# AJH_as3320_21_4hp.net
KiCad netlist of a schematic drawn in EAGLE
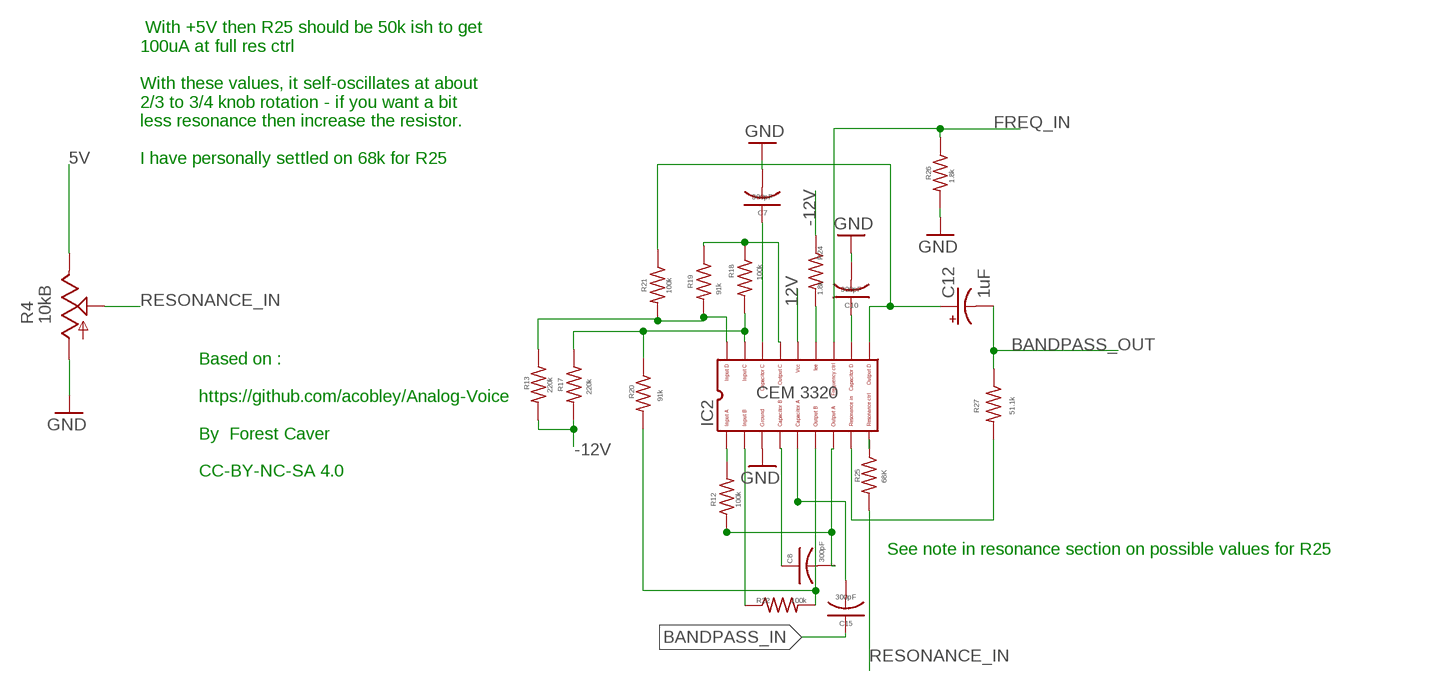
[diagram p0: schematic, sheet 1]
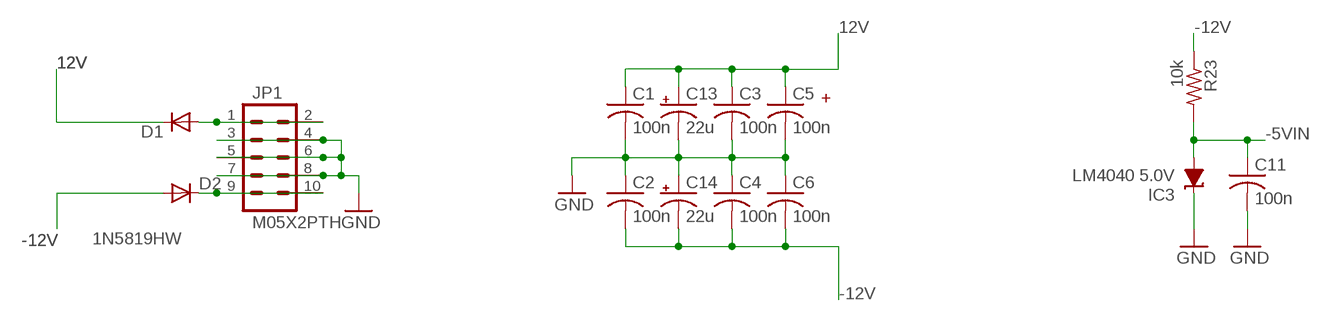
[diagram p1: schematic, sheet 2]
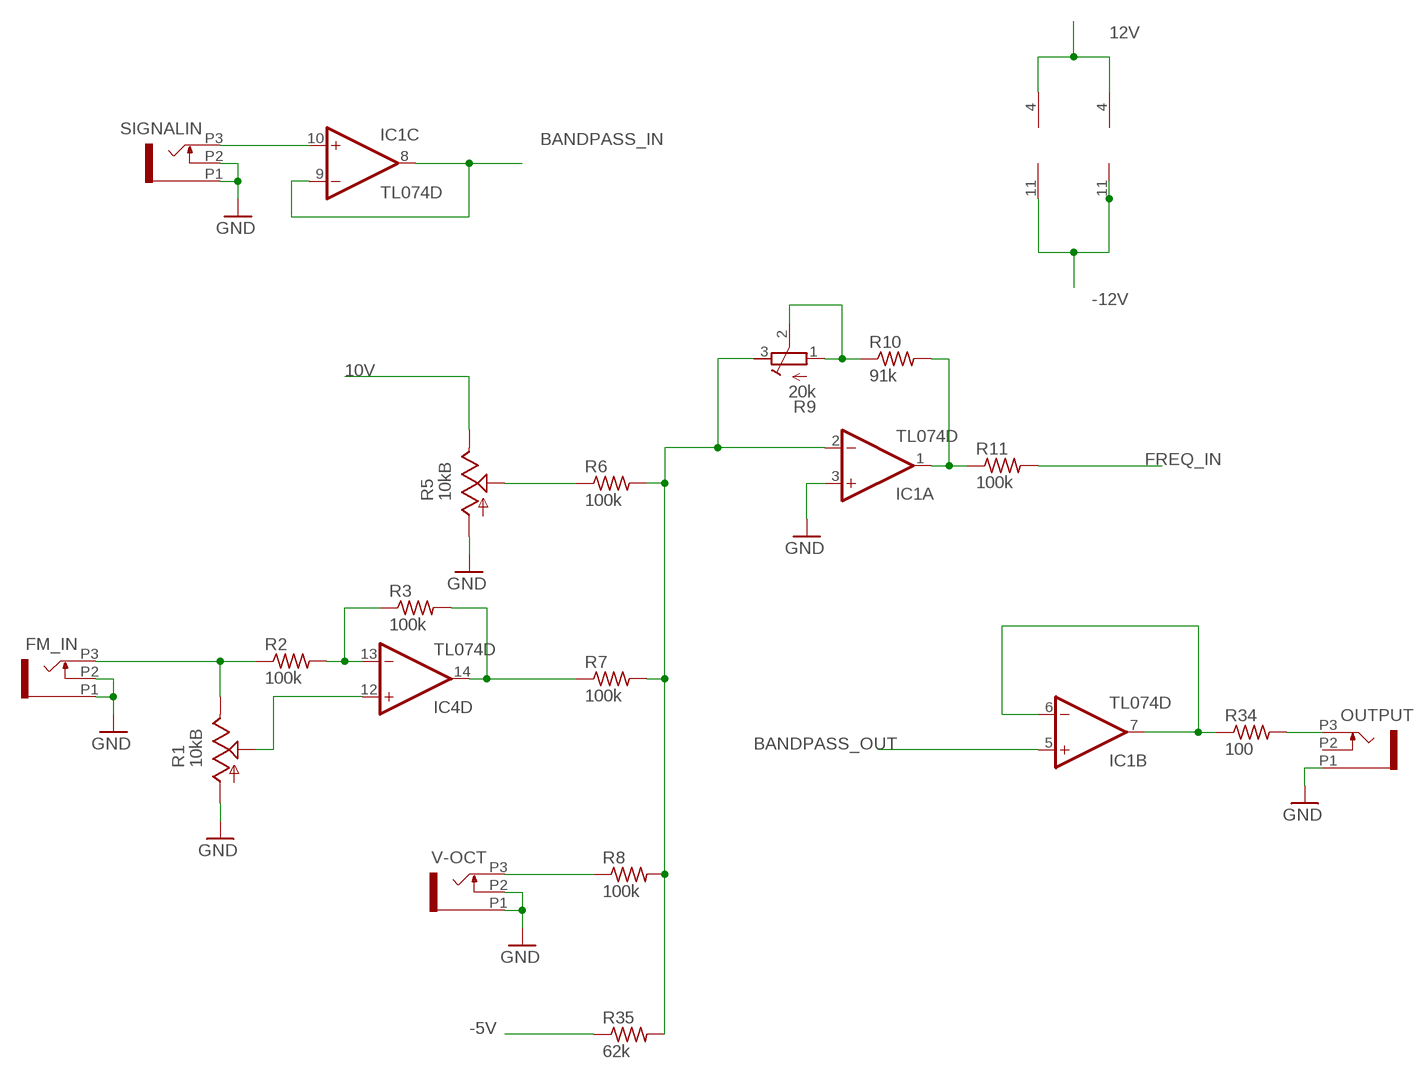
[diagram p2: schematic, sheet 3]
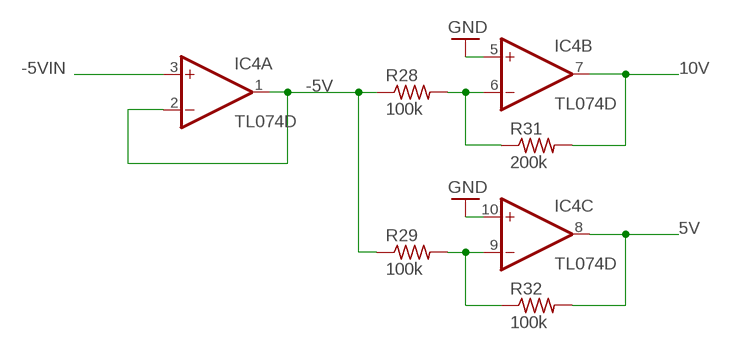
[diagram p3: schematic, sheet 4]

(export (version "E")
  (design (tool "Eeschema 10.0.6"))
  (components
    (comp (ref "IC4")
      (value "TL074D")
      (footprint "eagle-import:SO14")
      (libsource (lib "eagle-import") (part "TL074D"))
    )
    (comp (ref "R28")
      (value "100k")
      (footprint "eagle-import:R0603")
      (libsource (lib "eagle-import") (part "resistor_R-US_R0603"))
    )
    (comp (ref "R29")
      (value "100k")
      (footprint "eagle-import:R0603")
      (libsource (lib "eagle-import") (part "resistor_R-US_R0603"))
    )
    (comp (ref "R31")
      (value "200k")
      (footprint "eagle-import:R0603")
      (libsource (lib "eagle-import") (part "resistor_R-US_R0603"))
    )
    (comp (ref "R32")
      (value "100k")
      (footprint "eagle-import:R0603")
      (libsource (lib "eagle-import") (part "resistor_R-US_R0603"))
    )
    (comp (ref "FM_IN")
      (value "PJ301_THONKICONN6")
      (footprint "eagle-import:WQP_PJ_301M6")
      (libsource (lib "eagle-import") (part "PJ301_THONKICONN6"))
    )
    (comp (ref "IC1")
      (value "TL074D")
      (footprint "eagle-import:SO14")
      (libsource (lib "eagle-import") (part "TL074D"))
    )
    (comp (ref "OUTPUT")
      (value "PJ301_THONKICONN6")
      (footprint "eagle-import:WQP_PJ_301M6")
      (libsource (lib "eagle-import") (part "PJ301_THONKICONN6"))
    )
    (comp (ref "R1")
      (value "10kB")
      (footprint "eagle-import:ALPS_POT_VERTICAL")
      (libsource (lib "eagle-import") (part "POT_USVERTICAL"))
    )
    (comp (ref "R2")
      (value "100k")
      (footprint "eagle-import:R0603")
      (libsource (lib "eagle-import") (part "resistor_R-US_R0603"))
    )
    (comp (ref "R3")
      (value "100k")
      (footprint "eagle-import:R0603")
      (libsource (lib "eagle-import") (part "resistor_R-US_R0603"))
    )
    (comp (ref "R5")
      (value "10kB")
      (footprint "eagle-import:ALPS_POT_VERTICAL")
      (libsource (lib "eagle-import") (part "POT_USVERTICAL"))
    )
    (comp (ref "R6")
      (value "100k")
      (footprint "eagle-import:R0603")
      (libsource (lib "eagle-import") (part "resistor_R-US_R0603"))
    )
    (comp (ref "R7")
      (value "100k")
      (footprint "eagle-import:R0603")
      (libsource (lib "eagle-import") (part "resistor_R-US_R0603"))
    )
    (comp (ref "R8")
      (value "100k")
      (footprint "eagle-import:R0603")
      (libsource (lib "eagle-import") (part "resistor_R-US_R0603"))
    )
    (comp (ref "R9")
      (value "20k")
      (footprint "eagle-import:RTRIM3296X")
      (libsource (lib "eagle-import") (part "R-TRIMM3296X"))
    )
    (comp (ref "R10")
      (value "91k")
      (footprint "eagle-import:R0603")
      (libsource (lib "eagle-import") (part "resistor_R-US_R0603"))
    )
    (comp (ref "R11")
      (value "100k")
      (footprint "eagle-import:R0603")
      (libsource (lib "eagle-import") (part "resistor_R-US_R0603"))
    )
    (comp (ref "R34")
      (value "100")
      (footprint "eagle-import:R0603")
      (libsource (lib "eagle-import") (part "resistor_R-US_R0603"))
    )
    (comp (ref "R35")
      (value "62k")
      (footprint "eagle-import:R0603")
      (libsource (lib "eagle-import") (part "resistor_R-US_R0603"))
    )
    (comp (ref "SIGNALIN")
      (value "PJ301_THONKICONN6")
      (footprint "eagle-import:WQP_PJ_301M6")
      (libsource (lib "eagle-import") (part "PJ301_THONKICONN6"))
    )
    (comp (ref "V-OCT")
      (value "PJ301_THONKICONN6")
      (footprint "eagle-import:WQP_PJ_301M6")
      (libsource (lib "eagle-import") (part "PJ301_THONKICONN6"))
    )
    (comp (ref "C1")
      (value "100n")
      (footprint "eagle-import:C0603")
      (libsource (lib "eagle-import") (part "C-USC0603"))
    )
    (comp (ref "C2")
      (value "100n")
      (footprint "eagle-import:C0603")
      (libsource (lib "eagle-import") (part "C-USC0603"))
    )
    (comp (ref "C3")
      (value "100n")
      (footprint "eagle-import:C0603")
      (libsource (lib "eagle-import") (part "C-USC0603"))
    )
    (comp (ref "C4")
      (value "100n")
      (footprint "eagle-import:C0603")
      (libsource (lib "eagle-import") (part "C-USC0603"))
    )
    (comp (ref "C5")
      (value "100n")
      (footprint "eagle-import:C0603")
      (libsource (lib "eagle-import") (part "C-USC0603"))
    )
    (comp (ref "C6")
      (value "100n")
      (footprint "eagle-import:C0603")
      (libsource (lib "eagle-import") (part "C-USC0603"))
    )
    (comp (ref "C11")
      (value "100n")
      (footprint "eagle-import:C0603")
      (libsource (lib "eagle-import") (part "C-USC0603"))
    )
    (comp (ref "C13")
      (value "22u")
      (footprint "eagle-import:PANASONIC_B")
      (libsource (lib "eagle-import") (part "CPOL-USB"))
    )
    (comp (ref "C14")
      (value "22u")
      (footprint "eagle-import:PANASONIC_B")
      (libsource (lib "eagle-import") (part "CPOL-USB"))
    )
    (comp (ref "D1")
      (value "1N5819HW")
      (footprint "eagle-import:SOD123")
      (libsource (lib "eagle-import") (part "DIODE-SOD123"))
    )
    (comp (ref "D2")
      (value "1N5819HW")
      (footprint "eagle-import:SOD123")
      (libsource (lib "eagle-import") (part "DIODE-SOD123"))
    )
    (comp (ref "IC3")
      (value "LM4040 5.0V")
      (footprint "eagle-import:DBZ_R-PDSO-G3")
      (libsource (lib "eagle-import") (part "LM4041DBZC12"))
    )
    (comp (ref "JP1")
      (value "M05X2PTH")
      (footprint "eagle-import:AVR_ICSP")
      (libsource (lib "eagle-import") (part "M05X2PTH"))
    )
    (comp (ref "R23")
      (value "10k")
      (footprint "eagle-import:R0603")
      (libsource (lib "eagle-import") (part "resistor_R-US_R0603"))
    )
    (comp (ref "C7")
      (value "300pF")
      (footprint "eagle-import:C0603")
      (libsource (lib "eagle-import") (part "rcl_334_C-USC0603"))
    )
    (comp (ref "C8")
      (value "300pF")
      (footprint "eagle-import:C0603")
      (libsource (lib "eagle-import") (part "rcl_334_C-USC0603"))
    )
    (comp (ref "C10")
      (value "300pF")
      (footprint "eagle-import:C0603")
      (libsource (lib "eagle-import") (part "rcl_334_C-USC0603"))
    )
    (comp (ref "C12")
      (value "1uF")
      (footprint "eagle-import:PANASONIC_B")
      (libsource (lib "eagle-import") (part "rcl_334_CPOL-USB"))
    )
    (comp (ref "C15")
      (value "300pF")
      (footprint "eagle-import:C0603")
      (libsource (lib "eagle-import") (part "rcl_334_C-USC0603"))
    )
    (comp (ref "IC2")
      (value "CEM3320")
      (footprint "eagle-import:DIL18")
      (libsource (lib "eagle-import") (part "CEM3320"))
    )
    (comp (ref "R4")
      (value "10kB")
      (footprint "eagle-import:ALPS_POT_VERTICAL")
      (libsource (lib "eagle-import") (part "POT_USVERTICAL"))
    )
    (comp (ref "R12")
      (value "100k")
      (footprint "eagle-import:R0603")
      (libsource (lib "eagle-import") (part "R-US_R0603"))
    )
    (comp (ref "R13")
      (value "220k")
      (footprint "eagle-import:R0603")
      (libsource (lib "eagle-import") (part "R-US_R0603"))
    )
    (comp (ref "R17")
      (value "220k")
      (footprint "eagle-import:R0603")
      (libsource (lib "eagle-import") (part "R-US_R0603"))
    )
    (comp (ref "R18")
      (value "100k")
      (footprint "eagle-import:R0603")
      (libsource (lib "eagle-import") (part "R-US_R0603"))
    )
    (comp (ref "R19")
      (value "91k")
      (footprint "eagle-import:R0603")
      (libsource (lib "eagle-import") (part "R-US_R0603"))
    )
    (comp (ref "R20")
      (value "91k")
      (footprint "eagle-import:R0603")
      (libsource (lib "eagle-import") (part "R-US_R0603"))
    )
    (comp (ref "R21")
      (value "100k")
      (footprint "eagle-import:R0603")
      (libsource (lib "eagle-import") (part "R-US_R0603"))
    )
    (comp (ref "R22")
      (value "100k")
      (footprint "eagle-import:R0603")
      (libsource (lib "eagle-import") (part "R-US_R0603"))
    )
    (comp (ref "R24")
      (value "1.8k")
      (footprint "eagle-import:R0603")
      (libsource (lib "eagle-import") (part "R-US_R0603"))
    )
    (comp (ref "R25")
      (value "68K")
      (footprint "eagle-import:R0603")
      (libsource (lib "eagle-import") (part "R-US_R0603"))
    )
    (comp (ref "R26")
      (value "1.8k")
      (footprint "eagle-import:R0603")
      (libsource (lib "eagle-import") (part "R-US_R0603"))
    )
    (comp (ref "R27")
      (value "51.1k")
      (footprint "eagle-import:R0603")
      (libsource (lib "eagle-import") (part "R-US_R0603"))
    )
  )
  (nets
    (net (code "1") (name "-5V") (class "Default")
      (node (ref "IC4") (pin "1") (pinfunction "OUT_1") (pintype "output"))
      (node (ref "IC4") (pin "2") (pinfunction "-IN_2") (pintype "input"))
      (node (ref "R28") (pin "1") (pinfunction "1_1") (pintype "passive"))
      (node (ref "R29") (pin "1") (pinfunction "1_1") (pintype "passive"))
      (node (ref "R35") (pin "1") (pinfunction "1_1") (pintype "passive"))
    )
    (net (code "2") (name "-5VIN") (class "Default")
      (node (ref "C11") (pin "1") (pinfunction "1_1") (pintype "passive"))
      (node (ref "IC3") (pin "2") (pinfunction "A_2") (pintype "passive"))
      (node (ref "IC4") (pin "3") (pinfunction "+IN_3") (pintype "input"))
      (node (ref "R23") (pin "2") (pinfunction "2_2") (pintype "passive"))
    )
    (net (code "3") (name "-12V") (class "Default")
      (node (ref "C14") (pin "-") (pinfunction "-_-") (pintype "passive"))
      (node (ref "C2") (pin "2") (pinfunction "2_2") (pintype "passive"))
      (node (ref "C4") (pin "2") (pinfunction "2_2") (pintype "passive"))
      (node (ref "C6") (pin "2") (pinfunction "2_2") (pintype "passive"))
      (node (ref "D2") (pin "A") (pinfunction "A_A") (pintype "passive"))
      (node (ref "IC1") (pin "11") (pinfunction "V-_11") (pintype "power_in"))
      (node (ref "IC4") (pin "11") (pinfunction "V-_11") (pintype "power_in"))
      (node (ref "R13") (pin "2") (pinfunction "2_2") (pintype "passive"))
      (node (ref "R17") (pin "2") (pinfunction "2_2") (pintype "passive"))
      (node (ref "R23") (pin "1") (pinfunction "1_1") (pintype "passive"))
      (node (ref "R24") (pin "1") (pinfunction "1_1") (pintype "passive"))
    )
    (net (code "4") (name "5V") (class "Default")
      (node (ref "IC4") (pin "8") (pinfunction "OUT_8") (pintype "output"))
      (node (ref "R32") (pin "2") (pinfunction "2_2") (pintype "passive"))
      (node (ref "R4") (pin "P$1") (pinfunction "E_P$1") (pintype "passive"))
    )
    (net (code "5") (name "10V") (class "Default")
      (node (ref "IC4") (pin "7") (pinfunction "OUT_7") (pintype "output"))
      (node (ref "R31") (pin "2") (pinfunction "2_2") (pintype "passive"))
      (node (ref "R5") (pin "P$1") (pinfunction "E_P$1") (pintype "passive"))
    )
    (net (code "6") (name "12V") (class "Default")
      (node (ref "C1") (pin "1") (pinfunction "1_1") (pintype "passive"))
      (node (ref "C13") (pin "+") (pinfunction "+_+") (pintype "passive"))
      (node (ref "C3") (pin "1") (pinfunction "1_1") (pintype "passive"))
      (node (ref "C5") (pin "1") (pinfunction "1_1") (pintype "passive"))
      (node (ref "D1") (pin "C") (pinfunction "C_C") (pintype "passive"))
      (node (ref "IC1") (pin "4") (pinfunction "V+_4") (pintype "power_in"))
      (node (ref "IC2") (pin "14") (pinfunction "14_14") (pintype "power_in"))
      (node (ref "IC4") (pin "4") (pinfunction "V+_4") (pintype "power_in"))
    )
    (net (code "7") (name "BANDPASS_IN") (class "Default")
      (node (ref "C15") (pin "1") (pinfunction "1_1") (pintype "passive"))
      (node (ref "IC1") (pin "8") (pinfunction "OUT_8") (pintype "output"))
      (node (ref "IC1") (pin "9") (pinfunction "-IN_9") (pintype "input"))
    )
    (net (code "8") (name "BANDPASS_OUT") (class "Default")
      (node (ref "C12") (pin "-") (pinfunction "-_-") (pintype "passive"))
      (node (ref "IC1") (pin "5") (pinfunction "+IN_5") (pintype "input"))
      (node (ref "R27") (pin "1") (pinfunction "1_1") (pintype "passive"))
    )
    (net (code "9") (name "FREQ_IN") (class "Default")
      (node (ref "IC2") (pin "12") (pinfunction "12_12") (pintype "bidirectional"))
      (node (ref "R11") (pin "2") (pinfunction "2_2") (pintype "passive"))
      (node (ref "R26") (pin "1") (pinfunction "1_1") (pintype "passive"))
    )
    (net (code "10") (name "GND") (class "Default")
      (node (ref "C1") (pin "2") (pinfunction "2_2") (pintype "passive"))
      (node (ref "C10") (pin "2") (pinfunction "2_2") (pintype "passive"))
      (node (ref "C11") (pin "2") (pinfunction "2_2") (pintype "passive"))
      (node (ref "C13") (pin "-") (pinfunction "-_-") (pintype "passive"))
      (node (ref "C14") (pin "+") (pinfunction "+_+") (pintype "passive"))
      (node (ref "C2") (pin "1") (pinfunction "1_1") (pintype "passive"))
      (node (ref "C3") (pin "2") (pinfunction "2_2") (pintype "passive"))
      (node (ref "C4") (pin "1") (pinfunction "1_1") (pintype "passive"))
      (node (ref "C5") (pin "2") (pinfunction "2_2") (pintype "passive"))
      (node (ref "C6") (pin "1") (pinfunction "1_1") (pintype "passive"))
      (node (ref "C7") (pin "2") (pinfunction "2_2") (pintype "passive"))
      (node (ref "FM_IN") (pin "P1") (pinfunction "1_P1") (pintype "passive"))
      (node (ref "FM_IN") (pin "P2") (pinfunction "2_P2") (pintype "passive"))
      (node (ref "IC1") (pin "3") (pinfunction "+IN_3") (pintype "input"))
      (node (ref "IC2") (pin "3") (pinfunction "3_3") (pintype "power_in"))
      (node (ref "IC3") (pin "1") (pinfunction "C_1") (pintype "passive"))
      (node (ref "IC4") (pin "10") (pinfunction "+IN_10") (pintype "input"))
      (node (ref "IC4") (pin "5") (pinfunction "+IN_5") (pintype "input"))
      (node (ref "JP1") (pin "3") (pinfunction "3_3") (pintype "passive"))
      (node (ref "JP1") (pin "4") (pinfunction "4_4") (pintype "passive"))
      (node (ref "JP1") (pin "5") (pinfunction "5_5") (pintype "passive"))
      (node (ref "JP1") (pin "6") (pinfunction "6_6") (pintype "passive"))
      (node (ref "JP1") (pin "7") (pinfunction "7_7") (pintype "passive"))
      (node (ref "JP1") (pin "8") (pinfunction "8_8") (pintype "passive"))
      (node (ref "OUTPUT") (pin "P1") (pinfunction "1_P1") (pintype "passive"))
      (node (ref "R1") (pin "P$3") (pinfunction "A_P$3") (pintype "passive"))
      (node (ref "R26") (pin "2") (pinfunction "2_2") (pintype "passive"))
      (node (ref "R4") (pin "P$3") (pinfunction "A_P$3") (pintype "passive"))
      (node (ref "R5") (pin "P$3") (pinfunction "A_P$3") (pintype "passive"))
      (node (ref "SIGNALIN") (pin "P1") (pinfunction "1_P1") (pintype "passive"))
      (node (ref "SIGNALIN") (pin "P2") (pinfunction "2_P2") (pintype "passive"))
      (node (ref "V-OCT") (pin "P1") (pinfunction "1_P1") (pintype "passive"))
      (node (ref "V-OCT") (pin "P2") (pinfunction "2_P2") (pintype "passive"))
    )
    (net (code "11") (name "Net-(C7-Pad1)") (class "Default")
      (node (ref "C7") (pin "1") (pinfunction "1_1") (pintype "passive"))
      (node (ref "IC2") (pin "16") (pinfunction "16_16") (pintype "bidirectional"))
    )
    (net (code "12") (name "Net-(C8-Pad1)") (class "Default")
      (node (ref "C8") (pin "1") (pinfunction "1_1") (pintype "passive"))
      (node (ref "IC2") (pin "4") (pinfunction "4_4") (pintype "bidirectional"))
    )
    (net (code "13") (name "Net-(C8-Pad2)") (class "Default")
      (node (ref "C8") (pin "2") (pinfunction "2_2") (pintype "passive"))
      (node (ref "IC2") (pin "7") (pinfunction "7_7") (pintype "output"))
      (node (ref "R12") (pin "1") (pinfunction "1_1") (pintype "passive"))
    )
    (net (code "14") (name "Net-(C10-Pad1)") (class "Default")
      (node (ref "C10") (pin "1") (pinfunction "1_1") (pintype "passive"))
      (node (ref "IC2") (pin "11") (pinfunction "11_11") (pintype "output"))
    )
    (net (code "15") (name "Net-(C12-Pad+)") (class "Default")
      (node (ref "C12") (pin "+") (pinfunction "+_+") (pintype "passive"))
      (node (ref "IC2") (pin "10") (pinfunction "10_10") (pintype "output"))
      (node (ref "R21") (pin "1") (pinfunction "1_1") (pintype "passive"))
    )
    (net (code "16") (name "Net-(C15-Pad2)") (class "Default")
      (node (ref "C15") (pin "2") (pinfunction "2_2") (pintype "passive"))
      (node (ref "IC2") (pin "5") (pinfunction "5_5") (pintype "bidirectional"))
    )
    (net (code "17") (name "Net-(D1-PadA)") (class "Default")
      (node (ref "D1") (pin "A") (pinfunction "A_A") (pintype "passive"))
      (node (ref "JP1") (pin "1") (pinfunction "1_1") (pintype "passive"))
      (node (ref "JP1") (pin "2") (pinfunction "2_2") (pintype "passive"))
    )
    (net (code "18") (name "Net-(D2-PadC)") (class "Default")
      (node (ref "D2") (pin "C") (pinfunction "C_C") (pintype "passive"))
      (node (ref "JP1") (pin "10") (pinfunction "10_10") (pintype "passive"))
      (node (ref "JP1") (pin "9") (pinfunction "9_9") (pintype "passive"))
    )
    (net (code "19") (name "Net-(FM_IN-3)") (class "Default")
      (node (ref "FM_IN") (pin "P3") (pinfunction "3_P3") (pintype "passive"))
      (node (ref "R1") (pin "P$1") (pinfunction "E_P$1") (pintype "passive"))
      (node (ref "R2") (pin "1") (pinfunction "1_1") (pintype "passive"))
    )
    (net (code "20") (name "Net-(IC1A--IN)") (class "Default")
      (node (ref "IC1") (pin "2") (pinfunction "-IN_2") (pintype "input"))
      (node (ref "R35") (pin "2") (pinfunction "2_2") (pintype "passive"))
      (node (ref "R6") (pin "2") (pinfunction "2_2") (pintype "passive"))
      (node (ref "R7") (pin "2") (pinfunction "2_2") (pintype "passive"))
      (node (ref "R8") (pin "2") (pinfunction "2_2") (pintype "passive"))
      (node (ref "R9") (pin "3") (pinfunction "A_3") (pintype "passive"))
    )
    (net (code "21") (name "Net-(IC1A-OUT)") (class "Default")
      (node (ref "IC1") (pin "1") (pinfunction "OUT_1") (pintype "output"))
      (node (ref "R10") (pin "2") (pinfunction "2_2") (pintype "passive"))
      (node (ref "R11") (pin "1") (pinfunction "1_1") (pintype "passive"))
    )
    (net (code "22") (name "Net-(IC1B--IN)") (class "Default")
      (node (ref "IC1") (pin "6") (pinfunction "-IN_6") (pintype "input"))
      (node (ref "IC1") (pin "7") (pinfunction "OUT_7") (pintype "output"))
      (node (ref "R34") (pin "1") (pinfunction "1_1") (pintype "passive"))
    )
    (net (code "23") (name "Net-(IC1C-+IN)") (class "Default")
      (node (ref "IC1") (pin "10") (pinfunction "+IN_10") (pintype "input"))
      (node (ref "SIGNALIN") (pin "P3") (pinfunction "3_P3") (pintype "passive"))
    )
    (net (code "24") (name "Net-(IC2-Pad1)") (class "Default")
      (node (ref "IC2") (pin "1") (pinfunction "1_1") (pintype "input"))
      (node (ref "R12") (pin "2") (pinfunction "2_2") (pintype "passive"))
    )
    (net (code "25") (name "Net-(IC2-Pad2)") (class "Default")
      (node (ref "IC2") (pin "2") (pinfunction "2_2") (pintype "input"))
      (node (ref "R22") (pin "1") (pinfunction "1_1") (pintype "passive"))
    )
    (net (code "26") (name "Net-(IC2-Pad6)") (class "Default")
      (node (ref "IC2") (pin "6") (pinfunction "6_6") (pintype "output"))
      (node (ref "R20") (pin "2") (pinfunction "2_2") (pintype "passive"))
      (node (ref "R22") (pin "2") (pinfunction "2_2") (pintype "passive"))
    )
    (net (code "27") (name "Net-(IC2-Pad8)") (class "Default")
      (node (ref "IC2") (pin "8") (pinfunction "8_8") (pintype "input"))
      (node (ref "R27") (pin "2") (pinfunction "2_2") (pintype "passive"))
    )
    (net (code "28") (name "Net-(IC2-Pad9)") (class "Default")
      (node (ref "IC2") (pin "9") (pinfunction "9_9") (pintype "input"))
      (node (ref "R25") (pin "1") (pinfunction "1_1") (pintype "passive"))
    )
    (net (code "29") (name "Net-(IC2-Pad13)") (class "Default")
      (node (ref "IC2") (pin "13") (pinfunction "13_13") (pintype "power_in"))
      (node (ref "R24") (pin "2") (pinfunction "2_2") (pintype "passive"))
    )
    (net (code "30") (name "Net-(IC2-Pad15)") (class "Default")
      (node (ref "IC2") (pin "15") (pinfunction "15_15") (pintype "output"))
      (node (ref "R18") (pin "1") (pinfunction "1_1") (pintype "passive"))
      (node (ref "R19") (pin "1") (pinfunction "1_1") (pintype "passive"))
    )
    (net (code "31") (name "Net-(IC2-Pad17)") (class "Default")
      (node (ref "IC2") (pin "17") (pinfunction "17_17") (pintype "input"))
      (node (ref "R17") (pin "1") (pinfunction "1_1") (pintype "passive"))
      (node (ref "R18") (pin "2") (pinfunction "2_2") (pintype "passive"))
      (node (ref "R20") (pin "1") (pinfunction "1_1") (pintype "passive"))
    )
    (net (code "32") (name "Net-(IC2-Pad18)") (class "Default")
      (node (ref "IC2") (pin "18") (pinfunction "18_18") (pintype "input"))
      (node (ref "R13") (pin "1") (pinfunction "1_1") (pintype "passive"))
      (node (ref "R19") (pin "2") (pinfunction "2_2") (pintype "passive"))
      (node (ref "R21") (pin "2") (pinfunction "2_2") (pintype "passive"))
    )
    (net (code "33") (name "Net-(IC4B--IN)") (class "Default")
      (node (ref "IC4") (pin "6") (pinfunction "-IN_6") (pintype "input"))
      (node (ref "R28") (pin "2") (pinfunction "2_2") (pintype "passive"))
      (node (ref "R31") (pin "1") (pinfunction "1_1") (pintype "passive"))
    )
    (net (code "34") (name "Net-(IC4C--IN)") (class "Default")
      (node (ref "IC4") (pin "9") (pinfunction "-IN_9") (pintype "input"))
      (node (ref "R29") (pin "2") (pinfunction "2_2") (pintype "passive"))
      (node (ref "R32") (pin "1") (pinfunction "1_1") (pintype "passive"))
    )
    (net (code "35") (name "Net-(IC4D-+IN)") (class "Default")
      (node (ref "IC4") (pin "12") (pinfunction "+IN_12") (pintype "input"))
      (node (ref "R1") (pin "P$2") (pinfunction "S_P$2") (pintype "passive"))
    )
    (net (code "36") (name "Net-(IC4D--IN)") (class "Default")
      (node (ref "IC4") (pin "13") (pinfunction "-IN_13") (pintype "input"))
      (node (ref "R2") (pin "2") (pinfunction "2_2") (pintype "passive"))
      (node (ref "R3") (pin "1") (pinfunction "1_1") (pintype "passive"))
    )
    (net (code "37") (name "Net-(IC4D-OUT)") (class "Default")
      (node (ref "IC4") (pin "14") (pinfunction "OUT_14") (pintype "output"))
      (node (ref "R3") (pin "2") (pinfunction "2_2") (pintype "passive"))
      (node (ref "R7") (pin "1") (pinfunction "1_1") (pintype "passive"))
    )
    (net (code "38") (name "Net-(OUTPUT-3)") (class "Default")
      (node (ref "OUTPUT") (pin "P3") (pinfunction "3_P3") (pintype "passive"))
      (node (ref "R34") (pin "2") (pinfunction "2_2") (pintype "passive"))
    )
    (net (code "39") (name "Net-(R5-S)") (class "Default")
      (node (ref "R5") (pin "P$2") (pinfunction "S_P$2") (pintype "passive"))
      (node (ref "R6") (pin "1") (pinfunction "1_1") (pintype "passive"))
    )
    (net (code "40") (name "Net-(R9-E)") (class "Default")
      (node (ref "R10") (pin "1") (pinfunction "1_1") (pintype "passive"))
      (node (ref "R9") (pin "1") (pinfunction "E_1") (pintype "passive"))
      (node (ref "R9") (pin "2") (pinfunction "S_2") (pintype "passive"))
    )
    (net (code "41") (name "Net-(V-OCT-3)") (class "Default")
      (node (ref "R8") (pin "1") (pinfunction "1_1") (pintype "passive"))
      (node (ref "V-OCT") (pin "P3") (pinfunction "3_P3") (pintype "passive"))
    )
    (net (code "42") (name "RESONANCE_IN") (class "Default")
      (node (ref "R25") (pin "2") (pinfunction "2_2") (pintype "passive"))
      (node (ref "R4") (pin "P$2") (pinfunction "S_P$2") (pintype "passive"))
    )
    (net (code "43") (name "unconnected-(OUTPUT-2-PadP2)") (class "Default")
      (node (ref "OUTPUT") (pin "P2") (pinfunction "2_P2") (pintype "passive"))
    )
  )
)
